# CW308T_LPC55S69_Main.net
KiCad netlist of a schematic drawn in Altium Designer
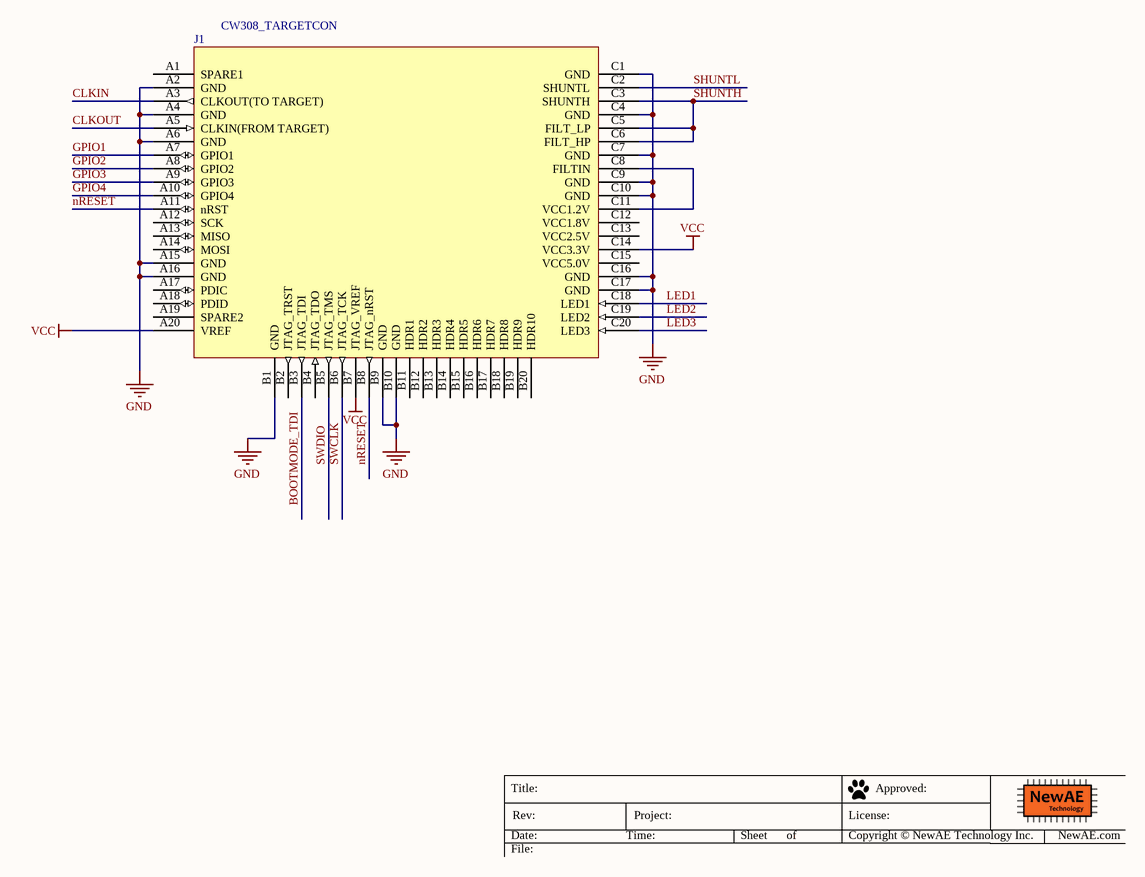
[diagram p0: CW308T_LPC55S69_Main.SchDoc]

(export (version "E")
  (design (tool "Eeschema 10.0.6"))
  (components
    (comp (ref "J1")
      (value "CW308_TARGETCON")
      (footprint "CW308_TBOARD_CONN")
      (description "CW308 \"Standard\" Target Board Connector")
      (fields (field (name "PART NUMBER") "CW308_TBOARD"))
      (libsource (lib "NewAE_AltiumLib") (part "CW308_TBOARD"))
    )
  )
  (nets
    (net (code "1") (name "/BOOTMODE_TDI") (class "Default")
      (node (ref "J1") (pin "B3") (pinfunction "JTAG_TDI_B3") (pintype "output"))
    )
    (net (code "2") (name "/CLKIN") (class "Default")
      (node (ref "J1") (pin "A3") (pinfunction "CLKOUT(TO_TARGET)_A3") (pintype "output"))
    )
    (net (code "3") (name "/CLKOUT") (class "Default")
      (node (ref "J1") (pin "A5") (pinfunction "CLKIN(FROM_TARGET)_A5") (pintype "input"))
    )
    (net (code "4") (name "/GPIO1") (class "Default")
      (node (ref "J1") (pin "A7") (pinfunction "GPIO1_A7") (pintype "bidirectional"))
    )
    (net (code "5") (name "/GPIO2") (class "Default")
      (node (ref "J1") (pin "A8") (pinfunction "GPIO2_A8") (pintype "bidirectional"))
    )
    (net (code "6") (name "/GPIO3") (class "Default")
      (node (ref "J1") (pin "A9") (pinfunction "GPIO3_A9") (pintype "bidirectional"))
    )
    (net (code "7") (name "/GPIO4") (class "Default")
      (node (ref "J1") (pin "A10") (pinfunction "GPIO4_A10") (pintype "bidirectional"))
    )
    (net (code "8") (name "/LED1") (class "Default")
      (node (ref "J1") (pin "C18") (pinfunction "LED1_C18") (pintype "input"))
    )
    (net (code "9") (name "/LED2") (class "Default")
      (node (ref "J1") (pin "C19") (pinfunction "LED2_C19") (pintype "input"))
    )
    (net (code "10") (name "/LED3") (class "Default")
      (node (ref "J1") (pin "C20") (pinfunction "LED3_C20") (pintype "input"))
    )
    (net (code "11") (name "/SHUNTH") (class "Default")
      (node (ref "J1") (pin "C3") (pinfunction "SHUNTH_C3") (pintype "passive"))
      (node (ref "J1") (pin "C5") (pinfunction "FILT_LP_C5") (pintype "passive"))
      (node (ref "J1") (pin "C6") (pinfunction "FILT_HP_C6") (pintype "passive"))
    )
    (net (code "12") (name "/SHUNTL") (class "Default")
      (node (ref "J1") (pin "C2") (pinfunction "SHUNTL_C2") (pintype "passive"))
    )
    (net (code "13") (name "/SWCLK") (class "Default")
      (node (ref "J1") (pin "B6") (pinfunction "JTAG_TCK_B6") (pintype "output"))
    )
    (net (code "14") (name "/SWDIO") (class "Default")
      (node (ref "J1") (pin "B5") (pinfunction "JTAG_TMS_B5") (pintype "output"))
    )
    (net (code "15") (name "/nRESET") (class "Default")
      (node (ref "J1") (pin "A11") (pinfunction "nRST_A11") (pintype "bidirectional"))
      (node (ref "J1") (pin "B8") (pinfunction "JTAG_nRST_B8") (pintype "output"))
    )
    (net (code "16") (name "GND") (class "Default")
      (node (ref "J1") (pin "A15") (pinfunction "GND_A15") (pintype "passive"))
      (node (ref "J1") (pin "A16") (pinfunction "GND_A16") (pintype "passive"))
      (node (ref "J1") (pin "A2") (pinfunction "GND_A2") (pintype "passive"))
      (node (ref "J1") (pin "A4") (pinfunction "GND_A4") (pintype "passive"))
      (node (ref "J1") (pin "A6") (pinfunction "GND_A6") (pintype "power_in"))
      (node (ref "J1") (pin "B1") (pinfunction "GND_B1") (pintype "passive"))
      (node (ref "J1") (pin "B10") (pinfunction "GND_B10") (pintype "passive"))
      (node (ref "J1") (pin "B9") (pinfunction "GND_B9") (pintype "passive"))
      (node (ref "J1") (pin "C1") (pinfunction "GND_C1") (pintype "power_in"))
      (node (ref "J1") (pin "C10") (pinfunction "GND_C10") (pintype "power_in"))
      (node (ref "J1") (pin "C16") (pinfunction "GND_C16") (pintype "power_in"))
      (node (ref "J1") (pin "C17") (pinfunction "GND_C17") (pintype "power_in"))
      (node (ref "J1") (pin "C4") (pinfunction "GND_C4") (pintype "power_in"))
      (node (ref "J1") (pin "C7") (pinfunction "GND_C7") (pintype "power_in"))
      (node (ref "J1") (pin "C9") (pinfunction "GND_C9") (pintype "power_in"))
    )
    (net (code "17") (name "Net-(J1-FILTIN)") (class "Default")
      (node (ref "J1") (pin "C11") (pinfunction "VCC1.2V_C11") (pintype "power_in"))
      (node (ref "J1") (pin "C8") (pinfunction "FILTIN_C8") (pintype "passive"))
    )
    (net (code "18") (name "VCC") (class "Default")
      (node (ref "J1") (pin "A20") (pinfunction "VREF_A20") (pintype "tri_state"))
      (node (ref "J1") (pin "B7") (pinfunction "JTAG_VREF_B7") (pintype "tri_state"))
      (node (ref "J1") (pin "C14") (pinfunction "VCC3.3V_C14") (pintype "power_in"))
    )
    (net (code "19") (name "unconnected-(J1-HDR1-PadB11)") (class "Default")
      (node (ref "J1") (pin "B11") (pinfunction "HDR1_B11") (pintype "passive"))
    )
    (net (code "20") (name "unconnected-(J1-HDR2-PadB12)") (class "Default")
      (node (ref "J1") (pin "B12") (pinfunction "HDR2_B12") (pintype "passive"))
    )
    (net (code "21") (name "unconnected-(J1-HDR3-PadB13)") (class "Default")
      (node (ref "J1") (pin "B13") (pinfunction "HDR3_B13") (pintype "passive"))
    )
    (net (code "22") (name "unconnected-(J1-HDR4-PadB14)") (class "Default")
      (node (ref "J1") (pin "B14") (pinfunction "HDR4_B14") (pintype "passive"))
    )
    (net (code "23") (name "unconnected-(J1-HDR5-PadB15)") (class "Default")
      (node (ref "J1") (pin "B15") (pinfunction "HDR5_B15") (pintype "passive"))
    )
    (net (code "24") (name "unconnected-(J1-HDR6-PadB16)") (class "Default")
      (node (ref "J1") (pin "B16") (pinfunction "HDR6_B16") (pintype "passive"))
    )
    (net (code "25") (name "unconnected-(J1-HDR7-PadB17)") (class "Default")
      (node (ref "J1") (pin "B17") (pinfunction "HDR7_B17") (pintype "passive"))
    )
    (net (code "26") (name "unconnected-(J1-HDR8-PadB18)") (class "Default")
      (node (ref "J1") (pin "B18") (pinfunction "HDR8_B18") (pintype "passive"))
    )
    (net (code "27") (name "unconnected-(J1-HDR9-PadB19)") (class "Default")
      (node (ref "J1") (pin "B19") (pinfunction "HDR9_B19") (pintype "passive"))
    )
    (net (code "28") (name "unconnected-(J1-HDR10-PadB20)") (class "Default")
      (node (ref "J1") (pin "B20") (pinfunction "HDR10_B20") (pintype "passive"))
    )
    (net (code "29") (name "unconnected-(J1-JTAG_TDO-PadB4)") (class "Default")
      (node (ref "J1") (pin "B4") (pinfunction "JTAG_TDO_B4") (pintype "input"))
    )
    (net (code "30") (name "unconnected-(J1-JTAG_TRST-PadB2)") (class "Default")
      (node (ref "J1") (pin "B2") (pinfunction "JTAG_TRST_B2") (pintype "output"))
    )
    (net (code "31") (name "unconnected-(J1-MISO-PadA13)") (class "Default")
      (node (ref "J1") (pin "A13") (pinfunction "MISO_A13") (pintype "bidirectional"))
    )
    (net (code "32") (name "unconnected-(J1-MOSI-PadA14)") (class "Default")
      (node (ref "J1") (pin "A14") (pinfunction "MOSI_A14") (pintype "bidirectional"))
    )
    (net (code "33") (name "unconnected-(J1-PDIC-PadA17)") (class "Default")
      (node (ref "J1") (pin "A17") (pinfunction "PDIC_A17") (pintype "bidirectional"))
    )
    (net (code "34") (name "unconnected-(J1-PDID-PadA18)") (class "Default")
      (node (ref "J1") (pin "A18") (pinfunction "PDID_A18") (pintype "bidirectional"))
    )
    (net (code "35") (name "unconnected-(J1-SCK-PadA12)") (class "Default")
      (node (ref "J1") (pin "A12") (pinfunction "SCK_A12") (pintype "bidirectional"))
    )
    (net (code "36") (name "unconnected-(J1-SPARE1-PadA1)") (class "Default")
      (node (ref "J1") (pin "A1") (pinfunction "SPARE1_A1") (pintype "passive"))
    )
    (net (code "37") (name "unconnected-(J1-SPARE2-PadA19)") (class "Default")
      (node (ref "J1") (pin "A19") (pinfunction "SPARE2_A19") (pintype "passive"))
    )
    (net (code "38") (name "unconnected-(J1-VCC1.8V-PadC12)") (class "Default")
      (node (ref "J1") (pin "C12") (pinfunction "VCC1.8V_C12") (pintype "power_in"))
    )
    (net (code "39") (name "unconnected-(J1-VCC2.5V-PadC13)") (class "Default")
      (node (ref "J1") (pin "C13") (pinfunction "VCC2.5V_C13") (pintype "power_in"))
    )
    (net (code "40") (name "unconnected-(J1-VCC5.0V-PadC15)") (class "Default")
      (node (ref "J1") (pin "C15") (pinfunction "VCC5.0V_C15") (pintype "power_in"))
    )
  )
)
